# TinyFoc_v1.net
KiCad netlist of a schematic drawn in Altium Designer
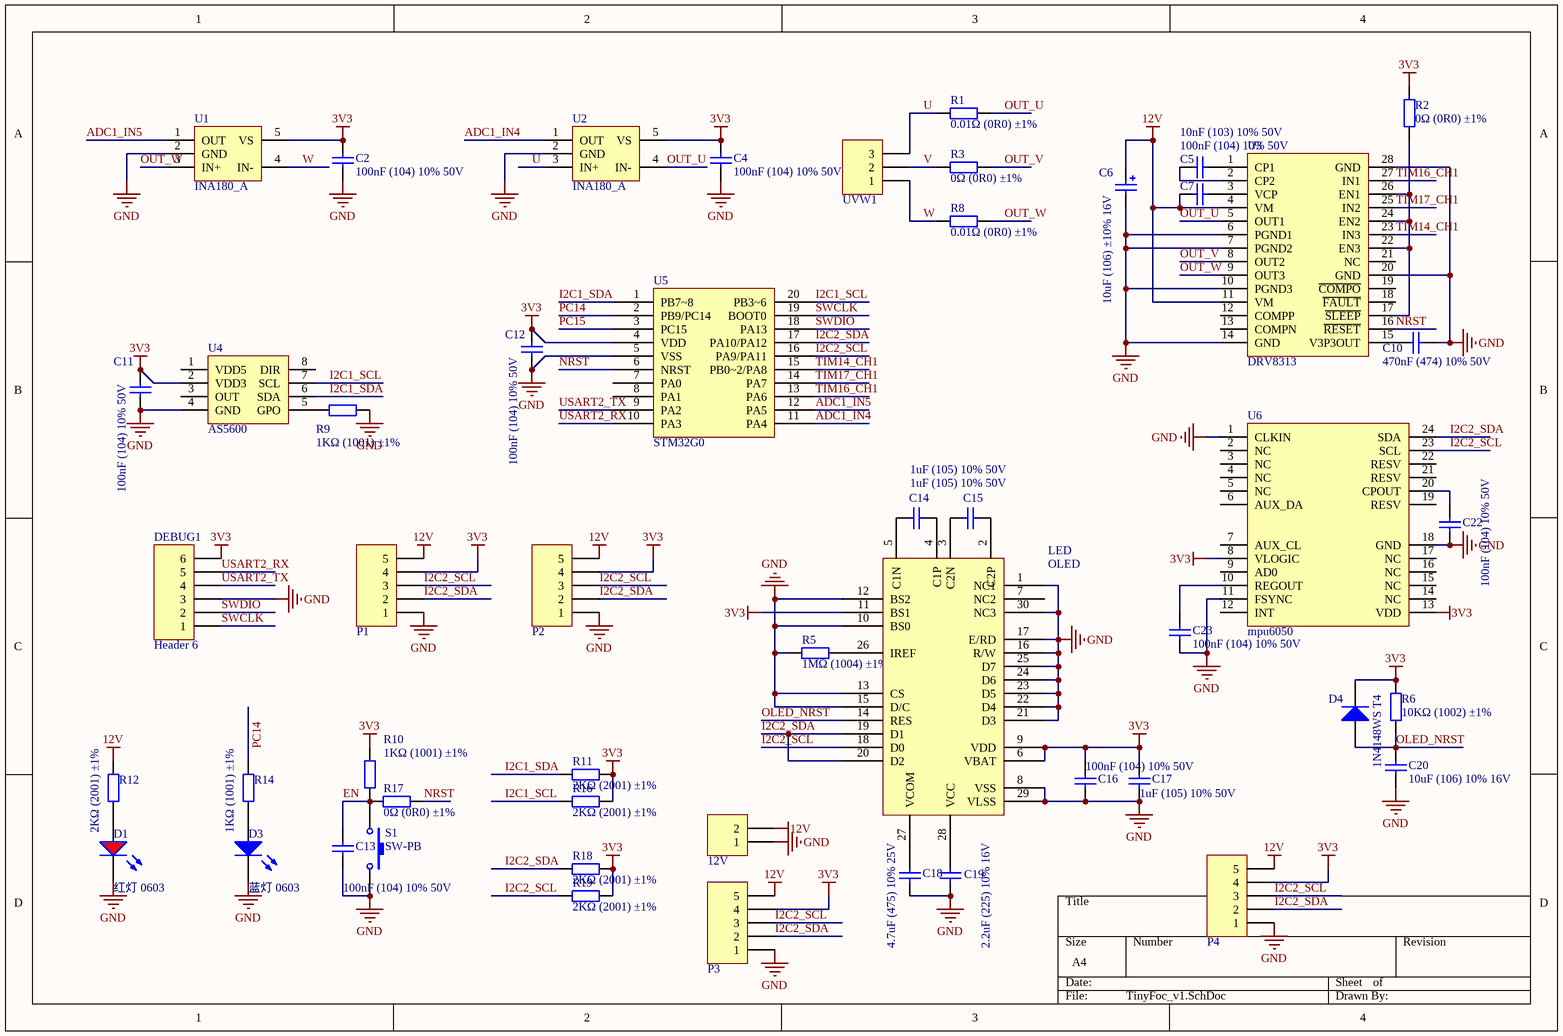
[diagram p0: TinyFoc_v1.SchDoc]

(export (version "E")
  (design (tool "Eeschema 10.0.6"))
  (components
    (comp (ref "12V")
      (value "Header 2")
      (footprint "HDR2X1_A")
      (description "接插件")
      (fields (field (name "PUBLISHER") "Altium Limited"))
      (libsource (lib "Devin_Lib") (part "Header 2"))
    )
    (comp (ref "C2")
      (value "100nF (104) 10% 50V")
      (footprint "0603_C")
      (description "贴片电容")
      (libsource (lib "Miscellaneous Devices LC") (part "0603 100nF (104) 10% 50V"))
    )
    (comp (ref "C4")
      (value "100nF (104) 10% 50V")
      (footprint "0603_C")
      (description "贴片电容")
      (libsource (lib "Miscellaneous Devices LC") (part "0603 100nF (104) 10% 50V"))
    )
    (comp (ref "C5")
      (value "10nF (103) 10% 50V")
      (footprint "0603_C")
      (description "贴片电容")
      (libsource (lib "Miscellaneous Devices LC") (part "0603 10nF (103) 10% 50V"))
    )
    (comp (ref "C6")
      (value "10uF (106) ±10% 16V")
      (footprint "CASE-B_3528")
      (description "钽电容")
      (libsource (lib "Miscellaneous Devices LC") (part "3528 100uF (107) 10% 6.3V"))
    )
    (comp (ref "C7")
      (value "100nF (104) 10% 50V")
      (footprint "0603_C")
      (description "贴片电容")
      (libsource (lib "Miscellaneous Devices LC") (part "0603 100nF (104) 10% 50V"))
    )
    (comp (ref "C10")
      (value "470nF (474) 10% 50V")
      (footprint "0805_C")
      (description "贴片电容")
      (libsource (lib "Miscellaneous Devices LC") (part "0805 470nF (474) 10% 50V"))
    )
    (comp (ref "C11")
      (value "100nF (104) 10% 50V")
      (footprint "0603_C")
      (description "贴片电容")
      (libsource (lib "Miscellaneous Devices LC") (part "0603 100nF (104) 10% 50V"))
    )
    (comp (ref "C12")
      (value "100nF (104) 10% 50V")
      (footprint "0603_C")
      (description "贴片电容")
      (libsource (lib "Miscellaneous Devices LC") (part "0603 100nF (104) 10% 50V"))
    )
    (comp (ref "C13")
      (value "100nF (104) 10% 50V")
      (footprint "0603_C")
      (description "贴片电容")
      (libsource (lib "Miscellaneous Devices LC") (part "0603 100nF (104) 10% 50V"))
    )
    (comp (ref "C14")
      (value "1uF (105) 10% 50V")
      (footprint "0603_C")
      (description "贴片电容")
      (libsource (lib "Miscellaneous Devices LC") (part "0603 1uF (105) 10% 50V"))
    )
    (comp (ref "C15")
      (value "1uF (105) 10% 50V")
      (footprint "0603_C")
      (description "贴片电容")
      (libsource (lib "Miscellaneous Devices LC") (part "0603 1uF (105) 10% 50V"))
    )
    (comp (ref "C16")
      (value "100nF (104) 10% 50V")
      (footprint "0603_C")
      (description "贴片电容")
      (libsource (lib "Miscellaneous Devices LC") (part "0603 100nF (104) 10% 50V"))
    )
    (comp (ref "C17")
      (value "1uF (105) 10% 50V")
      (footprint "0603_C")
      (description "贴片电容")
      (libsource (lib "Miscellaneous Devices LC") (part "0603 1uF (105) 10% 50V"))
    )
    (comp (ref "C18")
      (value "4.7uF (475) 10% 25V")
      (footprint "0805_C")
      (description "贴片电容")
      (libsource (lib "Miscellaneous Devices LC") (part "0805 4.7uF (475) 10% 25V"))
    )
    (comp (ref "C19")
      (value "2.2uF (225) 10% 16V")
      (footprint "0603_C")
      (description "贴片电容")
      (libsource (lib "Miscellaneous Devices LC") (part "0603 2.2uF (225) 10% 16V"))
    )
    (comp (ref "C20")
      (value "10uF (106) 10% 16V")
      (footprint "0805_C")
      (description "贴片电容")
      (libsource (lib "Miscellaneous Devices LC") (part "0805 10uF (106) 10% 25V"))
    )
    (comp (ref "C22")
      (value "100nF (104) 10% 50V")
      (footprint "0603_C")
      (description "贴片电容")
      (libsource (lib "Miscellaneous Devices LC") (part "0603 100nF (104) 10% 50V"))
    )
    (comp (ref "C23")
      (value "100nF (104) 10% 50V")
      (footprint "0603_C")
      (description "贴片电容")
      (libsource (lib "Miscellaneous Devices LC") (part "0603 100nF (104) 10% 50V"))
    )
    (comp (ref "D1")
      (value "红灯 0603")
      (footprint "0603_LED_S1")
      (description "发光二极管")
      (libsource (lib "Miscellaneous Devices LC") (part "0603 红灯"))
    )
    (comp (ref "D3")
      (value "蓝灯 0603")
      (footprint "0603_LED_S1")
      (description "发光二极管")
      (libsource (lib "Miscellaneous Devices LC") (part "0603 蓝灯"))
    )
    (comp (ref "D4")
      (value "1N4148WS T4")
      (footprint "SOD-323")
      (description "二极管")
      (libsource (lib "Miscellaneous Devices LC") (part "SOD-323 1N4148WS T4"))
    )
    (comp (ref "DEBUG1")
      (value "Header 6")
      (footprint "HDR6X1_A_2.0")
      (description "接插件")
      (fields (field (name "PUBLISHER") "Altium Limited"))
      (libsource (lib "Devin_Lib") (part "Header 6"))
    )
    (comp (ref "LED")
      (value "OLED")
      (footprint "OLED_pin30")
      (description "OLED显示屏12864")
      (libsource (lib "Devin_Lib") (part "OLED"))
    )
    (comp (ref "P1")
      (value "Header 5")
      (footprint "HDR5_1.27_A")
      (description "接插件-1.27")
      (fields (field (name "PUBLISHER") "Altium Limited"))
      (libsource (lib "Devin_Lib") (part "Header 5"))
    )
    (comp (ref "P2")
      (value "Header 5")
      (footprint "HDR5_1.27_A")
      (description "接插件-1.27")
      (fields (field (name "PUBLISHER") "Altium Limited"))
      (libsource (lib "Devin_Lib") (part "Header 5"))
    )
    (comp (ref "P3")
      (value "Header 5")
      (footprint "HDR5_1.27_A")
      (description "接插件-1.27")
      (fields (field (name "PUBLISHER") "Altium Limited"))
      (libsource (lib "Devin_Lib") (part "Header 5"))
    )
    (comp (ref "P4")
      (value "Header 5")
      (footprint "HDR5_1.27_B")
      (description "接插件-1.27")
      (fields (field (name "PUBLISHER") "Altium Limited"))
      (libsource (lib "Devin_Lib") (part "Header 5"))
    )
    (comp (ref "R1")
      (value "0.01Ω (0R0) ±1%")
      (footprint "0805_R")
      (description "贴片电阻")
      (libsource (lib "Miscellaneous Devices LC") (part "0805 0Ω (0R0) 1%"))
    )
    (comp (ref "R2")
      (value "0Ω (0R0) ±1%")
      (footprint "0402_R")
      (description "贴片电阻")
      (libsource (lib "") (part "0402 0Ω (0R0) 1%_1"))
    )
    (comp (ref "R3")
      (value "0Ω (0R0) ±1%")
      (footprint "0805_R")
      (description "贴片电阻")
      (libsource (lib "Miscellaneous Devices LC") (part "0805 0Ω (0R0) 1%"))
    )
    (comp (ref "R5")
      (value "1MΩ (1004) ±1%")
      (footprint "0603_R")
      (description "贴片电阻")
      (libsource (lib "Miscellaneous Devices LC") (part "0603 1MΩ (1004) 1%"))
    )
    (comp (ref "R6")
      (value "10KΩ (1002) ±1%")
      (footprint "0603_R")
      (description "贴片电阻")
      (libsource (lib "Miscellaneous Devices LC") (part "0603 10KΩ (1002) 1%"))
    )
    (comp (ref "R8")
      (value "0.01Ω (0R0) ±1%")
      (footprint "0805_R")
      (description "贴片电阻")
      (libsource (lib "Miscellaneous Devices LC") (part "0805 0Ω (0R0) 1%"))
    )
    (comp (ref "R9")
      (value "1KΩ (1001) ±1%")
      (footprint "0603_R")
      (description "贴片电阻")
      (libsource (lib "Miscellaneous Devices LC") (part "0603 1KΩ (1001) 1%"))
    )
    (comp (ref "R10")
      (value "1KΩ (1001) ±1%")
      (footprint "0603_R")
      (description "贴片电阻")
      (libsource (lib "") (part "0603 1KΩ (1001) 1%_1"))
    )
    (comp (ref "R11")
      (value "2KΩ (2001) ±1%")
      (footprint "0603_R")
      (description "贴片电阻")
      (libsource (lib "Miscellaneous Devices LC") (part "0603 2KΩ (2001) 1%"))
    )
    (comp (ref "R12")
      (value "2KΩ (2001) ±1%")
      (footprint "0805_R")
      (description "贴片电阻")
      (libsource (lib "Miscellaneous Devices LC") (part "0805 2KΩ (2001) 1%"))
    )
    (comp (ref "R14")
      (value "1KΩ (1001) ±1%")
      (footprint "0603_R")
      (description "贴片电阻")
      (libsource (lib "") (part "0603 1KΩ (1001) 1%_2"))
    )
    (comp (ref "R16")
      (value "2KΩ (2001) ±1%")
      (footprint "0603_R")
      (description "贴片电阻")
      (libsource (lib "Miscellaneous Devices LC") (part "0603 2KΩ (2001) 1%"))
    )
    (comp (ref "R17")
      (value "0Ω (0R0) ±1%")
      (footprint "0402_R")
      (description "贴片电阻")
      (libsource (lib "Miscellaneous Devices LC") (part "0402 0Ω (0R0) 1%"))
    )
    (comp (ref "R18")
      (value "2KΩ (2001) ±1%")
      (footprint "0603_R")
      (description "贴片电阻")
      (libsource (lib "Miscellaneous Devices LC") (part "0603 2KΩ (2001) 1%"))
    )
    (comp (ref "R19")
      (value "2KΩ (2001) ±1%")
      (footprint "0603_R")
      (description "贴片电阻")
      (libsource (lib "Miscellaneous Devices LC") (part "0603 2KΩ (2001) 1%"))
    )
    (comp (ref "S1")
      (value "SW-PB")
      (footprint "SW_PB2_3*5")
      (description "微动开关")
      (fields (field (name "PUBLISHER") "Altium Limited"))
      (libsource (lib "Devin_Lib") (part "SW-PB"))
    )
    (comp (ref "U1")
      (value "INA180_A")
      (footprint "SOT23")
      (description "电流检测")
      (libsource (lib "Devin_Lib") (part "INA180_A"))
    )
    (comp (ref "U2")
      (value "INA180_A")
      (footprint "SOT23")
      (description "电流检测")
      (libsource (lib "Devin_Lib") (part "INA180_A"))
    )
    (comp (ref "U3")
      (value "DRV8313")
      (footprint "TSSOP-28p")
      (description "无刷电机驱动芯片")
      (libsource (lib "Devin_Lib") (part "DRV8313"))
    )
    (comp (ref "U4")
      (value "AS5600")
      (footprint "SOP-8N")
      (description "磁编码器")
      (libsource (lib "Devin_Lib") (part "AS5600"))
    )
    (comp (ref "U5")
      (value "STM32G0")
      (footprint "STM8S103")
      (description "STM32单片机20引脚")
      (libsource (lib "Devin_Lib") (part "STM32G0"))
    )
    (comp (ref "U6")
      (value "mpu6050")
      (footprint "QFN50P400X400X80_HS-25N")
      (libsource (lib "Devin_Lib") (part "mpu6050"))
    )
    (comp (ref "UVW1")
      (value "Header 3")
      (footprint "HDR3X1_A")
      (description "接插件")
      (fields (field (name "PUBLISHER") "Altium Limited"))
      (libsource (lib "Devin_Lib") (part "Header 3"))
    )
  )
  (nets
    (net (code "1") (name "/ADC1_IN4") (class "Default")
      (node (ref "U2") (pin "1") (pinfunction "OUT_1") (pintype "passive"))
      (node (ref "U5") (pin "11") (pinfunction "PA4_11") (pintype "passive"))
    )
    (net (code "2") (name "/ADC1_IN5") (class "Default")
      (node (ref "U1") (pin "1") (pinfunction "OUT_1") (pintype "passive"))
      (node (ref "U5") (pin "12") (pinfunction "PA5_12") (pintype "passive"))
    )
    (net (code "3") (name "/EN") (class "Default")
      (node (ref "C13") (pin "2") (pinfunction "2_2") (pintype "passive"))
      (node (ref "R10") (pin "1") (pinfunction "1_1") (pintype "passive"))
      (node (ref "R17") (pin "2") (pinfunction "2_2") (pintype "passive"))
      (node (ref "S1") (pin "1") (pinfunction "1_1") (pintype "passive"))
    )
    (net (code "4") (name "/I2C1_SCL") (class "Default")
      (node (ref "R16") (pin "2") (pinfunction "2_2") (pintype "passive"))
      (node (ref "U4") (pin "7") (pinfunction "SCL_7") (pintype "passive"))
      (node (ref "U5") (pin "20") (pinfunction "PB3~6_20") (pintype "passive"))
    )
    (net (code "5") (name "/I2C1_SDA") (class "Default")
      (node (ref "R11") (pin "2") (pinfunction "2_2") (pintype "passive"))
      (node (ref "U4") (pin "6") (pinfunction "SDA_6") (pintype "passive"))
      (node (ref "U5") (pin "1") (pinfunction "PB7~8_1") (pintype "passive"))
    )
    (net (code "6") (name "/I2C2_SCL") (class "Default")
      (node (ref "LED") (pin "18") (pinfunction "D0_18") (pintype "passive"))
      (node (ref "P1") (pin "3") (pinfunction "3_3") (pintype "passive"))
      (node (ref "P2") (pin "3") (pinfunction "3_3") (pintype "passive"))
      (node (ref "P3") (pin "3") (pinfunction "3_3") (pintype "passive"))
      (node (ref "P4") (pin "3") (pinfunction "3_3") (pintype "passive"))
      (node (ref "R19") (pin "2") (pinfunction "2_2") (pintype "passive"))
      (node (ref "U5") (pin "16") (pinfunction "PA9/PA11_16") (pintype "passive"))
      (node (ref "U6") (pin "23") (pinfunction "SCL_23") (pintype "passive"))
    )
    (net (code "7") (name "/I2C2_SDA") (class "Default")
      (node (ref "LED") (pin "19") (pinfunction "D1_19") (pintype "passive"))
      (node (ref "LED") (pin "20") (pinfunction "D2_20") (pintype "passive"))
      (node (ref "P1") (pin "2") (pinfunction "2_2") (pintype "passive"))
      (node (ref "P2") (pin "2") (pinfunction "2_2") (pintype "passive"))
      (node (ref "P3") (pin "2") (pinfunction "2_2") (pintype "passive"))
      (node (ref "P4") (pin "2") (pinfunction "2_2") (pintype "passive"))
      (node (ref "R18") (pin "2") (pinfunction "2_2") (pintype "passive"))
      (node (ref "U5") (pin "17") (pinfunction "PA10/PA12_17") (pintype "passive"))
      (node (ref "U6") (pin "24") (pinfunction "SDA_24") (pintype "passive"))
    )
    (net (code "8") (name "/NRST") (class "Default")
      (node (ref "R17") (pin "1") (pinfunction "1_1") (pintype "passive"))
      (node (ref "U3") (pin "16") (pinfunction "~{RESET}_16") (pintype "passive"))
      (node (ref "U5") (pin "6") (pinfunction "NRST_6") (pintype "passive"))
    )
    (net (code "9") (name "/OLED_NRST") (class "Default")
      (node (ref "C20") (pin "2") (pinfunction "2_2") (pintype "passive"))
      (node (ref "D4") (pin "1") (pinfunction "A_1") (pintype "passive"))
      (node (ref "LED") (pin "14") (pinfunction "RES_14") (pintype "passive"))
      (node (ref "R6") (pin "1") (pinfunction "1_1") (pintype "passive"))
    )
    (net (code "10") (name "/OUT_U") (class "Default")
      (node (ref "R1") (pin "2") (pinfunction "2_2") (pintype "passive"))
      (node (ref "U2") (pin "4") (pinfunction "IN-_4") (pintype "passive"))
      (node (ref "U3") (pin "5") (pinfunction "OUT1_5") (pintype "passive"))
    )
    (net (code "11") (name "/OUT_V") (class "Default")
      (node (ref "R3") (pin "2") (pinfunction "2_2") (pintype "passive"))
      (node (ref "U3") (pin "8") (pinfunction "OUT2_8") (pintype "passive"))
    )
    (net (code "12") (name "/OUT_W") (class "Default")
      (node (ref "R8") (pin "2") (pinfunction "2_2") (pintype "passive"))
      (node (ref "U1") (pin "3") (pinfunction "IN+_3") (pintype "passive"))
      (node (ref "U3") (pin "9") (pinfunction "OUT3_9") (pintype "passive"))
    )
    (net (code "13") (name "/PC14") (class "Default")
      (node (ref "R14") (pin "1") (pinfunction "1_1") (pintype "passive"))
      (node (ref "U5") (pin "2") (pinfunction "PB9/PC14_2") (pintype "passive"))
    )
    (net (code "14") (name "/PC15") (class "Default")
      (node (ref "U5") (pin "3") (pinfunction "PC15_3") (pintype "passive"))
    )
    (net (code "15") (name "/SWCLK") (class "Default")
      (node (ref "DEBUG1") (pin "1") (pinfunction "1_1") (pintype "passive"))
      (node (ref "U5") (pin "19") (pinfunction "BOOT0_19") (pintype "passive"))
    )
    (net (code "16") (name "/SWDIO") (class "Default")
      (node (ref "DEBUG1") (pin "2") (pinfunction "2_2") (pintype "passive"))
      (node (ref "U5") (pin "18") (pinfunction "PA13_18") (pintype "passive"))
    )
    (net (code "17") (name "/TIM14_CH1") (class "Default")
      (node (ref "U3") (pin "23") (pinfunction "IN3_23") (pintype "passive"))
      (node (ref "U5") (pin "15") (pinfunction "PB0~2/PA8_15") (pintype "passive"))
    )
    (net (code "18") (name "/TIM16_CH1") (class "Default")
      (node (ref "U3") (pin "27") (pinfunction "IN1_27") (pintype "passive"))
      (node (ref "U5") (pin "13") (pinfunction "PA6_13") (pintype "passive"))
    )
    (net (code "19") (name "/TIM17_CH1") (class "Default")
      (node (ref "U3") (pin "25") (pinfunction "IN2_25") (pintype "passive"))
      (node (ref "U5") (pin "14") (pinfunction "PA7_14") (pintype "passive"))
    )
    (net (code "20") (name "/U") (class "Default")
      (node (ref "R1") (pin "1") (pinfunction "1_1") (pintype "passive"))
      (node (ref "U2") (pin "3") (pinfunction "IN+_3") (pintype "passive"))
      (node (ref "UVW1") (pin "3") (pinfunction "3_3") (pintype "passive"))
    )
    (net (code "21") (name "/USART2_RX") (class "Default")
      (node (ref "DEBUG1") (pin "5") (pinfunction "5_5") (pintype "passive"))
      (node (ref "U5") (pin "10") (pinfunction "PA3_10") (pintype "passive"))
    )
    (net (code "22") (name "/USART2_TX") (class "Default")
      (node (ref "DEBUG1") (pin "4") (pinfunction "4_4") (pintype "passive"))
      (node (ref "U5") (pin "9") (pinfunction "PA2_9") (pintype "passive"))
    )
    (net (code "23") (name "/V") (class "Default")
      (node (ref "R3") (pin "1") (pinfunction "1_1") (pintype "passive"))
      (node (ref "UVW1") (pin "2") (pinfunction "2_2") (pintype "passive"))
    )
    (net (code "24") (name "/W") (class "Default")
      (node (ref "R8") (pin "1") (pinfunction "1_1") (pintype "passive"))
      (node (ref "U1") (pin "4") (pinfunction "IN-_4") (pintype "passive"))
      (node (ref "UVW1") (pin "1") (pinfunction "1_1") (pintype "passive"))
    )
    (net (code "25") (name "3V3") (class "Default")
      (node (ref "C11") (pin "2") (pinfunction "2_2") (pintype "passive"))
      (node (ref "C12") (pin "2") (pinfunction "2_2") (pintype "passive"))
      (node (ref "C16") (pin "2") (pinfunction "2_2") (pintype "passive"))
      (node (ref "C17") (pin "2") (pinfunction "2_2") (pintype "passive"))
      (node (ref "C2") (pin "2") (pinfunction "2_2") (pintype "passive"))
      (node (ref "C4") (pin "2") (pinfunction "2_2") (pintype "passive"))
      (node (ref "D4") (pin "2") (pinfunction "K_2") (pintype "passive"))
      (node (ref "DEBUG1") (pin "6") (pinfunction "6_6") (pintype "passive"))
      (node (ref "LED") (pin "11") (pinfunction "BS1_11") (pintype "passive"))
      (node (ref "LED") (pin "6") (pinfunction "VBAT_6") (pintype "passive"))
      (node (ref "LED") (pin "9") (pinfunction "VDD_9") (pintype "passive"))
      (node (ref "P1") (pin "4") (pinfunction "4_4") (pintype "passive"))
      (node (ref "P2") (pin "4") (pinfunction "4_4") (pintype "passive"))
      (node (ref "P3") (pin "4") (pinfunction "4_4") (pintype "passive"))
      (node (ref "P4") (pin "4") (pinfunction "4_4") (pintype "passive"))
      (node (ref "R10") (pin "2") (pinfunction "2_2") (pintype "passive"))
      (node (ref "R11") (pin "1") (pinfunction "1_1") (pintype "passive"))
      (node (ref "R16") (pin "1") (pinfunction "1_1") (pintype "passive"))
      (node (ref "R18") (pin "1") (pinfunction "1_1") (pintype "passive"))
      (node (ref "R19") (pin "1") (pinfunction "1_1") (pintype "passive"))
      (node (ref "R2") (pin "1") (pinfunction "1_1") (pintype "passive"))
      (node (ref "R6") (pin "2") (pinfunction "2_2") (pintype "passive"))
      (node (ref "U1") (pin "5") (pinfunction "VS_5") (pintype "passive"))
      (node (ref "U2") (pin "5") (pinfunction "VS_5") (pintype "passive"))
      (node (ref "U4") (pin "2") (pinfunction "VDD3_2") (pintype "passive"))
      (node (ref "U5") (pin "4") (pinfunction "VDD_4") (pintype "passive"))
      (node (ref "U6") (pin "13") (pinfunction "VDD_13") (pintype "passive"))
      (node (ref "U6") (pin "8") (pinfunction "VLOGIC_8") (pintype "passive"))
    )
    (net (code "26") (name "12V") (class "Default")
      (node (ref "12V") (pin "2") (pinfunction "2_2") (pintype "passive"))
      (node (ref "C6") (pin "1") (pinfunction "1_1") (pintype "passive"))
      (node (ref "C7") (pin "1") (pinfunction "1_1") (pintype "passive"))
      (node (ref "P1") (pin "5") (pinfunction "5_5") (pintype "passive"))
      (node (ref "P2") (pin "5") (pinfunction "5_5") (pintype "passive"))
      (node (ref "P3") (pin "5") (pinfunction "5_5") (pintype "passive"))
      (node (ref "P4") (pin "5") (pinfunction "5_5") (pintype "passive"))
      (node (ref "R12") (pin "2") (pinfunction "2_2") (pintype "passive"))
      (node (ref "U3") (pin "11") (pinfunction "VM_11") (pintype "passive"))
      (node (ref "U3") (pin "4") (pinfunction "VM_4") (pintype "passive"))
    )
    (net (code "27") (name "GND") (class "Default")
      (node (ref "12V") (pin "1") (pinfunction "1_1") (pintype "passive"))
      (node (ref "C10") (pin "2") (pinfunction "2_2") (pintype "passive"))
      (node (ref "C11") (pin "1") (pinfunction "1_1") (pintype "passive"))
      (node (ref "C12") (pin "1") (pinfunction "1_1") (pintype "passive"))
      (node (ref "C13") (pin "1") (pinfunction "1_1") (pintype "passive"))
      (node (ref "C16") (pin "1") (pinfunction "1_1") (pintype "passive"))
      (node (ref "C17") (pin "1") (pinfunction "1_1") (pintype "passive"))
      (node (ref "C18") (pin "1") (pinfunction "1_1") (pintype "passive"))
      (node (ref "C19") (pin "1") (pinfunction "1_1") (pintype "passive"))
      (node (ref "C2") (pin "1") (pinfunction "1_1") (pintype "passive"))
      (node (ref "C20") (pin "1") (pinfunction "1_1") (pintype "passive"))
      (node (ref "C22") (pin "1") (pinfunction "1_1") (pintype "passive"))
      (node (ref "C23") (pin "1") (pinfunction "1_1") (pintype "passive"))
      (node (ref "C4") (pin "1") (pinfunction "1_1") (pintype "passive"))
      (node (ref "C6") (pin "2") (pinfunction "2_2") (pintype "passive"))
      (node (ref "D1") (pin "K") (pinfunction "K_K") (pintype "passive"))
      (node (ref "D3") (pin "K") (pinfunction "K_K") (pintype "passive"))
      (node (ref "DEBUG1") (pin "3") (pinfunction "3_3") (pintype "passive"))
      (node (ref "LED") (pin "1") (pinfunction "NC1_1") (pintype "passive"))
      (node (ref "LED") (pin "10") (pinfunction "BS0_10") (pintype "passive"))
      (node (ref "LED") (pin "12") (pinfunction "BS2_12") (pintype "passive"))
      (node (ref "LED") (pin "13") (pinfunction "CS_13") (pintype "passive"))
      (node (ref "LED") (pin "15") (pinfunction "D/C_15") (pintype "passive"))
      (node (ref "LED") (pin "16") (pinfunction "R/W_16") (pintype "passive"))
      (node (ref "LED") (pin "17") (pinfunction "E/RD_17") (pintype "passive"))
      (node (ref "LED") (pin "21") (pinfunction "D3_21") (pintype "passive"))
      (node (ref "LED") (pin "22") (pinfunction "D4_22") (pintype "passive"))
      (node (ref "LED") (pin "23") (pinfunction "D5_23") (pintype "passive"))
      (node (ref "LED") (pin "24") (pinfunction "D6_24") (pintype "passive"))
      (node (ref "LED") (pin "25") (pinfunction "D7_25") (pintype "passive"))
      (node (ref "LED") (pin "29") (pinfunction "VLSS_29") (pintype "passive"))
      (node (ref "LED") (pin "30") (pinfunction "NC3_30") (pintype "passive"))
      (node (ref "LED") (pin "8") (pinfunction "VSS_8") (pintype "passive"))
      (node (ref "P1") (pin "1") (pinfunction "1_1") (pintype "passive"))
      (node (ref "P2") (pin "1") (pinfunction "1_1") (pintype "passive"))
      (node (ref "P3") (pin "1") (pinfunction "1_1") (pintype "passive"))
      (node (ref "P4") (pin "1") (pinfunction "1_1") (pintype "passive"))
      (node (ref "R5") (pin "1") (pinfunction "1_1") (pintype "passive"))
      (node (ref "R9") (pin "2") (pinfunction "2_2") (pintype "passive"))
      (node (ref "S1") (pin "2") (pinfunction "2_2") (pintype "passive"))
      (node (ref "U1") (pin "2") (pinfunction "GND_2") (pintype "passive"))
      (node (ref "U2") (pin "2") (pinfunction "GND_2") (pintype "passive"))
      (node (ref "U3") (pin "10") (pinfunction "PGND3_10") (pintype "passive"))
      (node (ref "U3") (pin "14") (pinfunction "GND_14") (pintype "passive"))
      (node (ref "U3") (pin "20") (pinfunction "GND_20") (pintype "passive"))
      (node (ref "U3") (pin "28") (pinfunction "GND_28") (pintype "passive"))
      (node (ref "U3") (pin "6") (pinfunction "PGND1_6") (pintype "passive"))
      (node (ref "U3") (pin "7") (pinfunction "PGND2_7") (pintype "passive"))
      (node (ref "U4") (pin "4") (pinfunction "GND_4") (pintype "passive"))
      (node (ref "U5") (pin "5") (pinfunction "VSS_5") (pintype "passive"))
      (node (ref "U6") (pin "1") (pinfunction "CLKIN_1") (pintype "passive"))
      (node (ref "U6") (pin "11") (pinfunction "FSYNC_11") (pintype "passive"))
      (node (ref "U6") (pin "18") (pinfunction "GND_18") (pintype "passive"))
    )
    (net (code "28") (name "Net-(D1-PadA)") (class "Default")
      (node (ref "D1") (pin "A") (pinfunction "A_A") (pintype "passive"))
      (node (ref "R12") (pin "1") (pinfunction "1_1") (pintype "passive"))
    )
    (net (code "29") (name "Net-(D3-PadA)") (class "Default")
      (node (ref "D3") (pin "A") (pinfunction "A_A") (pintype "passive"))
      (node (ref "R14") (pin "2") (pinfunction "2_2") (pintype "passive"))
    )
    (net (code "30") (name "Net-(LED-C1N)") (class "Default")
      (node (ref "C14") (pin "1") (pinfunction "1_1") (pintype "passive"))
      (node (ref "LED") (pin "5") (pinfunction "C1N_5") (pintype "passive"))
    )
    (net (code "31") (name "Net-(LED-C1P)") (class "Default")
      (node (ref "C14") (pin "2") (pinfunction "2_2") (pintype "passive"))
      (node (ref "LED") (pin "4") (pinfunction "C1P_4") (pintype "passive"))
    )
    (net (code "32") (name "Net-(LED-C2N)") (class "Default")
      (node (ref "C15") (pin "1") (pinfunction "1_1") (pintype "passive"))
      (node (ref "LED") (pin "3") (pinfunction "C2N_3") (pintype "passive"))
    )
    (net (code "33") (name "Net-(LED-C2P)") (class "Default")
      (node (ref "C15") (pin "2") (pinfunction "2_2") (pintype "passive"))
      (node (ref "LED") (pin "2") (pinfunction "C2P_2") (pintype "passive"))
    )
    (net (code "34") (name "Net-(LED-IREF)") (class "Default")
      (node (ref "LED") (pin "26") (pinfunction "IREF_26") (pintype "passive"))
      (node (ref "R5") (pin "2") (pinfunction "2_2") (pintype "passive"))
    )
    (net (code "35") (name "Net-(LED-VCC)") (class "Default")
      (node (ref "C19") (pin "2") (pinfunction "2_2") (pintype "passive"))
      (node (ref "LED") (pin "28") (pinfunction "VCC_28") (pintype "passive"))
    )
    (net (code "36") (name "Net-(LED-VCOM)") (class "Default")
      (node (ref "C18") (pin "2") (pinfunction "2_2") (pintype "passive"))
      (node (ref "LED") (pin "27") (pinfunction "VCOM_27") (pintype "passive"))
    )
    (net (code "37") (name "Net-(U3-CP1)") (class "Default")
      (node (ref "C5") (pin "1") (pinfunction "1_1") (pintype "passive"))
      (node (ref "U3") (pin "1") (pinfunction "CP1_1") (pintype "passive"))
    )
    (net (code "38") (name "Net-(U3-CP2)") (class "Default")
      (node (ref "C5") (pin "2") (pinfunction "2_2") (pintype "passive"))
      (node (ref "U3") (pin "2") (pinfunction "CP2_2") (pintype "passive"))
    )
    (net (code "39") (name "Net-(U3-EN1)") (class "Default")
      (node (ref "R2") (pin "2") (pinfunction "2_2") (pintype "passive"))
      (node (ref "U3") (pin "17") (pinfunction "~{SLEEP}_17") (pintype "passive"))
      (node (ref "U3") (pin "22") (pinfunction "EN3_22") (pintype "passive"))
      (node (ref "U3") (pin "24") (pinfunction "EN2_24") (pintype "passive"))
      (node (ref "U3") (pin "26") (pinfunction "EN1_26") (pintype "passive"))
    )
    (net (code "40") (name "Net-(U3-V3P3OUT)") (class "Default")
      (node (ref "C10") (pin "1") (pinfunction "1_1") (pintype "passive"))
      (node (ref "U3") (pin "15") (pinfunction "V3P3OUT_15") (pintype "passive"))
    )
    (net (code "41") (name "Net-(U3-VCP)") (class "Default")
      (node (ref "C7") (pin "2") (pinfunction "2_2") (pintype "passive"))
      (node (ref "U3") (pin "3") (pinfunction "VCP_3") (pintype "passive"))
    )
    (net (code "42") (name "Net-(U4-GPO)") (class "Default")
      (node (ref "R9") (pin "1") (pinfunction "1_1") (pintype "passive"))
      (node (ref "U4") (pin "5") (pinfunction "GPO_5") (pintype "passive"))
    )
    (net (code "43") (name "Net-(U6-CPOUT)") (class "Default")
      (node (ref "C22") (pin "2") (pinfunction "2_2") (pintype "passive"))
      (node (ref "U6") (pin "20") (pinfunction "CPOUT_20") (pintype "passive"))
    )
    (net (code "44") (name "Net-(U6-REGOUT)") (class "Default")
      (node (ref "C23") (pin "2") (pinfunction "2_2") (pintype "passive"))
      (node (ref "U6") (pin "10") (pinfunction "REGOUT_10") (pintype "passive"))
    )
    (net (code "45") (name "unconnected-(LED-NC2-Pad7)") (class "Default")
      (node (ref "LED") (pin "7") (pinfunction "NC2_7") (pintype "passive"))
    )
    (net (code "46") (name "unconnected-(U3-COMPN-Pad13)") (class "Default")
      (node (ref "U3") (pin "13") (pinfunction "COMPN_13") (pintype "passive"))
    )
    (net (code "47") (name "unconnected-(U3-COMPP-Pad12)") (class "Default")
      (node (ref "U3") (pin "12") (pinfunction "COMPP_12") (pintype "passive"))
    )
    (net (code "48") (name "unconnected-(U3-NC-Pad21)") (class "Default")
      (node (ref "U3") (pin "21") (pinfunction "NC_21") (pintype "passive"))
    )
    (net (code "49") (name "unconnected-(U3-~{COMPO}-Pad19)") (class "Default")
      (node (ref "U3") (pin "19") (pinfunction "~{COMPO}_19") (pintype "passive"))
    )
    (net (code "50") (name "unconnected-(U3-~{FAULT}-Pad18)") (class "Default")
      (node (ref "U3") (pin "18") (pinfunction "~{FAULT}_18") (pintype "passive"))
    )
    (net (code "51") (name "unconnected-(U4-DIR-Pad8)") (class "Default")
      (node (ref "U4") (pin "8") (pinfunction "DIR_8") (pintype "passive"))
    )
    (net (code "52") (name "unconnected-(U4-OUT-Pad3)") (class "Default")
      (node (ref "U4") (pin "3") (pinfunction "OUT_3") (pintype "passive"))
    )
    (net (code "53") (name "unconnected-(U4-VDD5-Pad1)") (class "Default")
      (node (ref "U4") (pin "1") (pinfunction "VDD5_1") (pintype "passive"))
    )
    (net (code "54") (name "unconnected-(U5-PA0-Pad7)") (class "Default")
      (node (ref "U5") (pin "7") (pinfunction "PA0_7") (pintype "passive"))
    )
    (net (code "55") (name "unconnected-(U5-PA1-Pad8)") (class "Default")
      (node (ref "U5") (pin "8") (pinfunction "PA1_8") (pintype "passive"))
    )
    (net (code "56") (name "unconnected-(U6-AD0-Pad9)") (class "Default")
      (node (ref "U6") (pin "9") (pinfunction "AD0_9") (pintype "passive"))
    )
    (net (code "57") (name "unconnected-(U6-AUX_CL-Pad7)") (class "Default")
      (node (ref "U6") (pin "7") (pinfunction "AUX_CL_7") (pintype "passive"))
    )
    (net (code "58") (name "unconnected-(U6-AUX_DA-Pad6)") (class "Default")
      (node (ref "U6") (pin "6") (pinfunction "AUX_DA_6") (pintype "passive"))
    )
    (net (code "59") (name "unconnected-(U6-INT-Pad12)") (class "Default")
      (node (ref "U6") (pin "12") (pinfunction "INT_12") (pintype "passive"))
    )
    (net (code "60") (name "unconnected-(U6-NC-Pad2)") (class "Default")
      (node (ref "U6") (pin "2") (pinfunction "NC_2") (pintype "passive"))
    )
    (net (code "61") (name "unconnected-(U6-NC-Pad3)") (class "Default")
      (node (ref "U6") (pin "3") (pinfunction "NC_3") (pintype "passive"))
    )
    (net (code "62") (name "unconnected-(U6-NC-Pad4)") (class "Default")
      (node (ref "U6") (pin "4") (pinfunction "NC_4") (pintype "passive"))
    )
    (net (code "63") (name "unconnected-(U6-NC-Pad5)") (class "Default")
      (node (ref "U6") (pin "5") (pinfunction "NC_5") (pintype "passive"))
    )
    (net (code "64") (name "unconnected-(U6-NC-Pad14)") (class "Default")
      (node (ref "U6") (pin "14") (pinfunction "NC_14") (pintype "passive"))
    )
    (net (code "65") (name "unconnected-(U6-NC-Pad15)") (class "Default")
      (node (ref "U6") (pin "15") (pinfunction "NC_15") (pintype "passive"))
    )
    (net (code "66") (name "unconnected-(U6-NC-Pad16)") (class "Default")
      (node (ref "U6") (pin "16") (pinfunction "NC_16") (pintype "passive"))
    )
    (net (code "67") (name "unconnected-(U6-NC-Pad17)") (class "Default")
      (node (ref "U6") (pin "17") (pinfunction "NC_17") (pintype "passive"))
    )
    (net (code "68") (name "unconnected-(U6-RESV-Pad19)") (class "Default")
      (node (ref "U6") (pin "19") (pinfunction "RESV_19") (pintype "passive"))
    )
    (net (code "69") (name "unconnected-(U6-RESV-Pad21)") (class "Default")
      (node (ref "U6") (pin "21") (pinfunction "RESV_21") (pintype "passive"))
    )
    (net (code "70") (name "unconnected-(U6-RESV-Pad22)") (class "Default")
      (node (ref "U6") (pin "22") (pinfunction "RESV_22") (pintype "passive"))
    )
  )
)
